# Nebenplatine.net
KiCad netlist of a schematic drawn in EAGLE
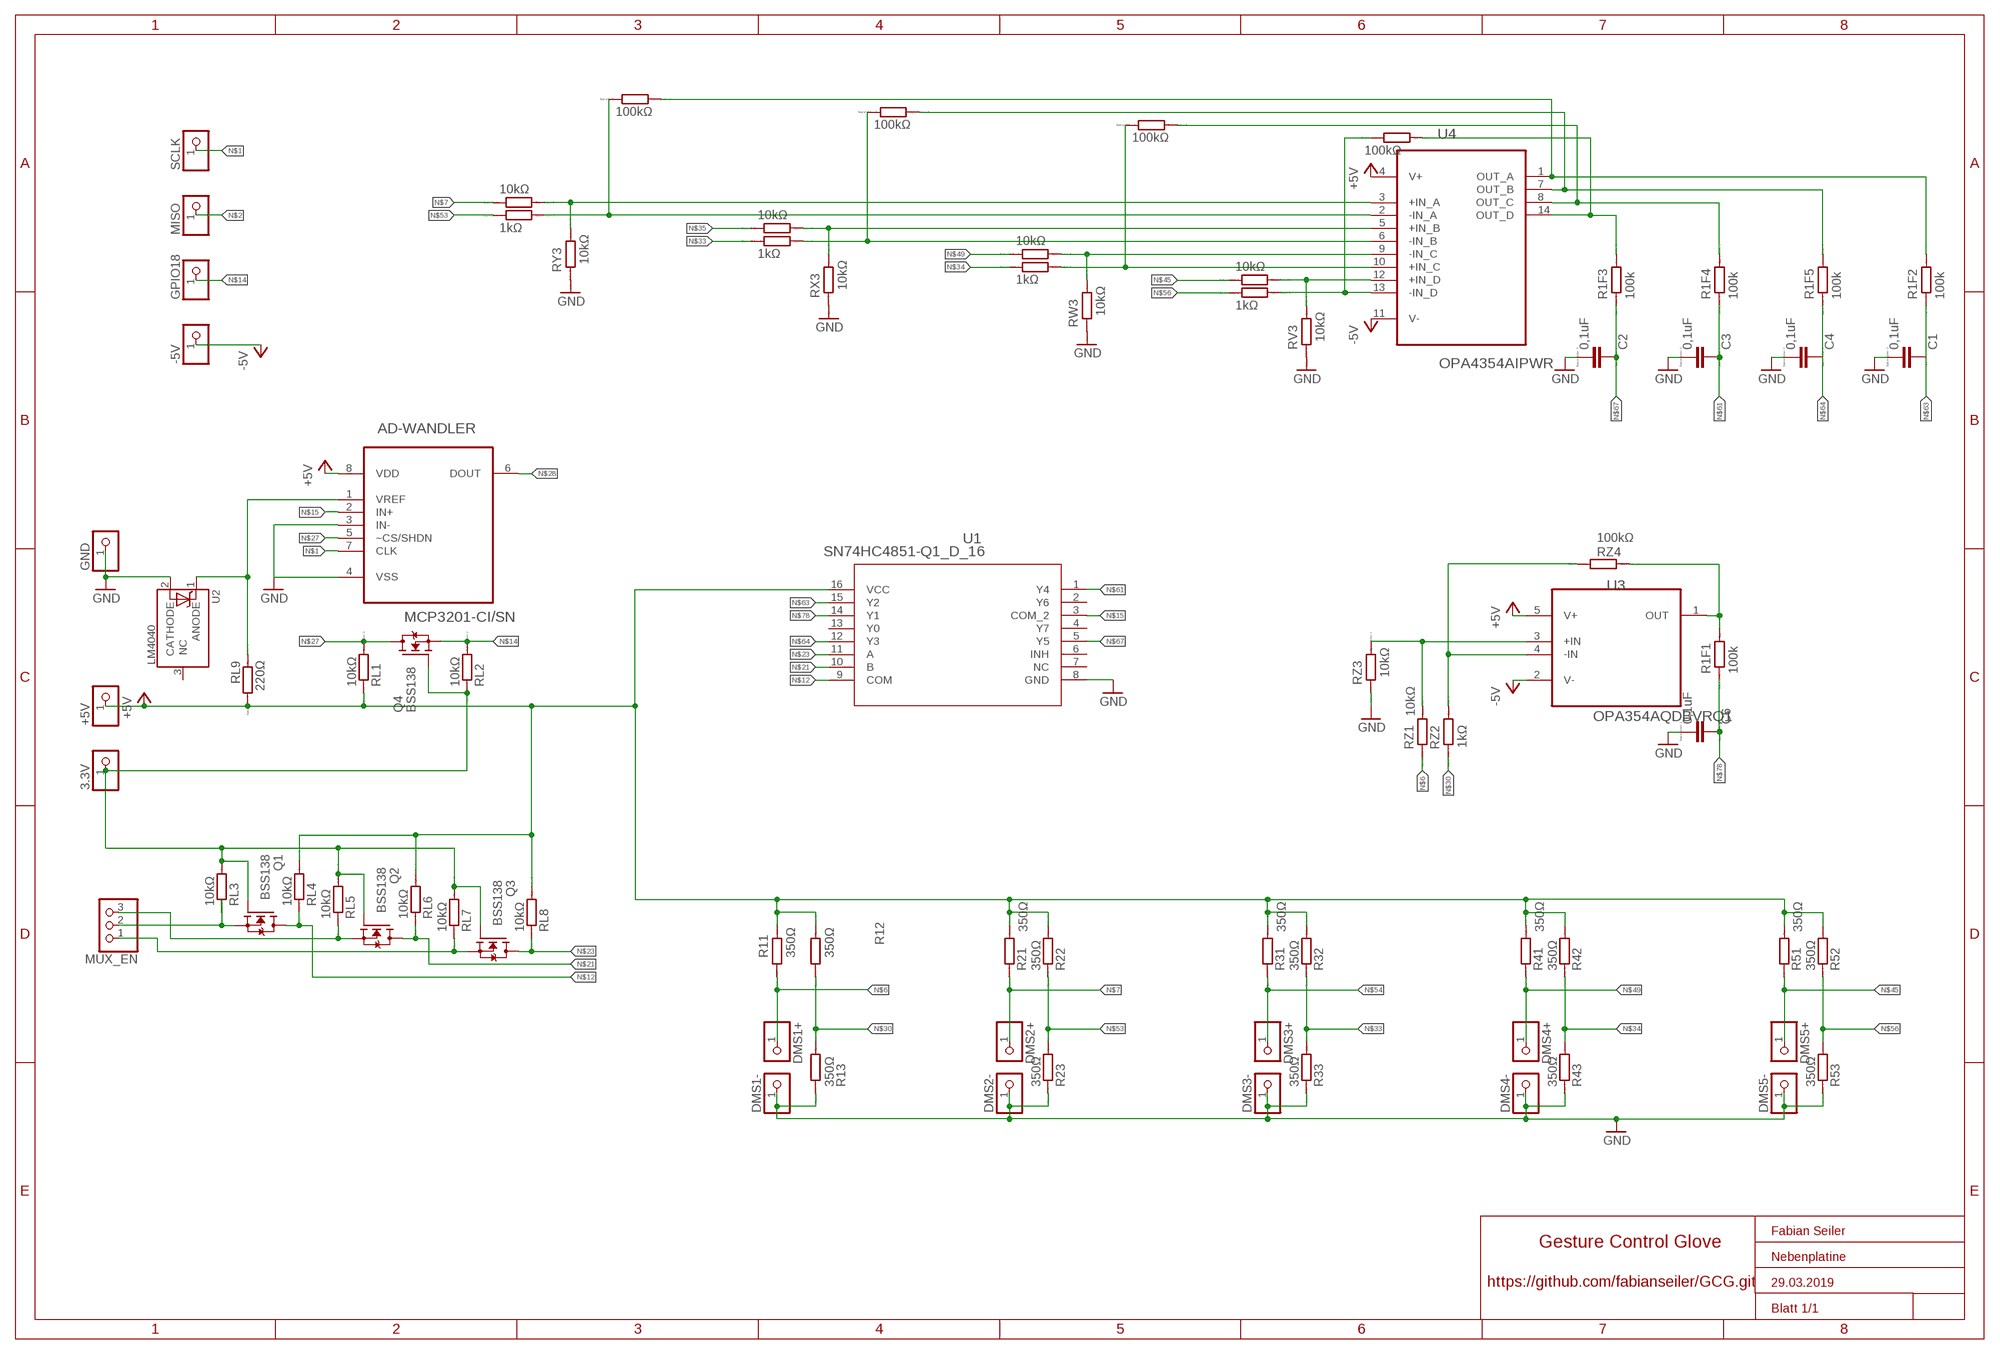
[diagram p0: schematic, sheet 1]

(export (version "E")
  (design (tool "Eeschema 10.0.6"))
  (components
    (comp (ref "+5V")
      (value "PINHD-1X1CB")
      (footprint "eagle-import:1X01-CLEANBIG")
      (libsource (lib "eagle-import") (part "PINHD-1X1CB"))
    )
    (comp (ref "-5V")
      (value "PINHD-1X1CB")
      (footprint "eagle-import:1X01-CLEANBIG")
      (libsource (lib "eagle-import") (part "PINHD-1X1CB"))
    )
    (comp (ref "3.3V")
      (value "PINHD-1X1CB")
      (footprint "eagle-import:1X01-CLEANBIG")
      (libsource (lib "eagle-import") (part "PINHD-1X1CB"))
    )
    (comp (ref "AD-WANDLER")
      (value "MCP3201-CI/SN")
      (footprint "eagle-import:SOIC127P600X175-8N")
      (fields (field (name "MF") "Microchip"))
      (libsource (lib "eagle-import") (part "MCP3201-CI/SN"))
    )
    (comp (ref "C1")
      (value "0,1uF")
      (footprint "eagle-import:C0402")
      (libsource (lib "eagle-import") (part "C-EUC0402"))
    )
    (comp (ref "C2")
      (value "0,1uF")
      (footprint "eagle-import:C0402")
      (libsource (lib "eagle-import") (part "C-EUC0402"))
    )
    (comp (ref "C3")
      (value "0,1uF")
      (footprint "eagle-import:C0402")
      (libsource (lib "eagle-import") (part "C-EUC0402"))
    )
    (comp (ref "C4")
      (value "0,1uF")
      (footprint "eagle-import:C0402")
      (libsource (lib "eagle-import") (part "C-EUC0402"))
    )
    (comp (ref "C6")
      (value "0,1uF")
      (footprint "eagle-import:C0402")
      (libsource (lib "eagle-import") (part "C-EUC0402"))
    )
    (comp (ref "DMS1+")
      (value "PINHD-1X1CB")
      (footprint "eagle-import:1X01-CLEANBIG")
      (libsource (lib "eagle-import") (part "PINHD-1X1CB"))
    )
    (comp (ref "DMS1-")
      (value "PINHD-1X1CB")
      (footprint "eagle-import:1X01-CLEANBIG")
      (libsource (lib "eagle-import") (part "PINHD-1X1CB"))
    )
    (comp (ref "DMS2+")
      (value "PINHD-1X1CB")
      (footprint "eagle-import:1X01-CLEANBIG")
      (libsource (lib "eagle-import") (part "PINHD-1X1CB"))
    )
    (comp (ref "DMS2-")
      (value "PINHD-1X1CB")
      (footprint "eagle-import:1X01-CLEANBIG")
      (libsource (lib "eagle-import") (part "PINHD-1X1CB"))
    )
    (comp (ref "DMS3+")
      (value "PINHD-1X1CB")
      (footprint "eagle-import:1X01-CLEANBIG")
      (libsource (lib "eagle-import") (part "PINHD-1X1CB"))
    )
    (comp (ref "DMS3-")
      (value "PINHD-1X1CB")
      (footprint "eagle-import:1X01-CLEANBIG")
      (libsource (lib "eagle-import") (part "PINHD-1X1CB"))
    )
    (comp (ref "DMS4+")
      (value "PINHD-1X1CB")
      (footprint "eagle-import:1X01-CLEANBIG")
      (libsource (lib "eagle-import") (part "PINHD-1X1CB"))
    )
    (comp (ref "DMS4-")
      (value "PINHD-1X1CB")
      (footprint "eagle-import:1X01-CLEANBIG")
      (libsource (lib "eagle-import") (part "PINHD-1X1CB"))
    )
    (comp (ref "DMS5+")
      (value "PINHD-1X1CB")
      (footprint "eagle-import:1X01-CLEANBIG")
      (libsource (lib "eagle-import") (part "PINHD-1X1CB"))
    )
    (comp (ref "DMS5-")
      (value "PINHD-1X1CB")
      (footprint "eagle-import:1X01-CLEANBIG")
      (libsource (lib "eagle-import") (part "PINHD-1X1CB"))
    )
    (comp (ref "GND")
      (value "PINHD-1X1CB")
      (footprint "eagle-import:1X01-CLEANBIG")
      (libsource (lib "eagle-import") (part "PINHD-1X1CB"))
    )
    (comp (ref "GPIO18")
      (value "PINHD-1X1CB")
      (footprint "eagle-import:1X01-CLEANBIG")
      (libsource (lib "eagle-import") (part "PINHD-1X1CB"))
    )
    (comp (ref "MISO")
      (value "PINHD-1X1CB")
      (footprint "eagle-import:1X01-CLEANBIG")
      (libsource (lib "eagle-import") (part "PINHD-1X1CB"))
    )
    (comp (ref "MUX_EN")
      (value "PINHD-1X3CB")
      (footprint "eagle-import:1X03-CLEANBIG")
      (libsource (lib "eagle-import") (part "PINHD-1X3CB"))
    )
    (comp (ref "Q1")
      (value "BSS138")
      (footprint "eagle-import:SOT23")
      (fields (field (name "MF") "Fairchild"))
      (libsource (lib "eagle-import") (part "BSS138"))
    )
    (comp (ref "Q2")
      (value "BSS138")
      (footprint "eagle-import:SOT23")
      (fields (field (name "MF") "Fairchild"))
      (libsource (lib "eagle-import") (part "BSS138"))
    )
    (comp (ref "Q3")
      (value "BSS138")
      (footprint "eagle-import:SOT23")
      (fields (field (name "MF") "Fairchild"))
      (libsource (lib "eagle-import") (part "BSS138"))
    )
    (comp (ref "Q4")
      (value "BSS138")
      (footprint "eagle-import:SOT23")
      (fields (field (name "MF") "Fairchild"))
      (libsource (lib "eagle-import") (part "BSS138"))
    )
    (comp (ref "R1F1")
      (value "100k")
      (footprint "eagle-import:R0402")
      (libsource (lib "eagle-import") (part "R-EU_R0402"))
    )
    (comp (ref "R1F2")
      (value "100k")
      (footprint "eagle-import:R0402")
      (libsource (lib "eagle-import") (part "R-EU_R0402"))
    )
    (comp (ref "R1F3")
      (value "100k")
      (footprint "eagle-import:R0402")
      (libsource (lib "eagle-import") (part "R-EU_R0402"))
    )
    (comp (ref "R1F4")
      (value "100k")
      (footprint "eagle-import:R0402")
      (libsource (lib "eagle-import") (part "R-EU_R0402"))
    )
    (comp (ref "R1F5")
      (value "100k")
      (footprint "eagle-import:R0402")
      (libsource (lib "eagle-import") (part "R-EU_R0402"))
    )
    (comp (ref "R11")
      (value "350Ω")
      (footprint "eagle-import:R0402")
      (libsource (lib "eagle-import") (part "R-EU_R0402"))
    )
    (comp (ref "R12")
      (value "350Ω")
      (footprint "eagle-import:R0402")
      (libsource (lib "eagle-import") (part "R-EU_R0402"))
    )
    (comp (ref "R13")
      (value "350Ω")
      (footprint "eagle-import:R0402")
      (libsource (lib "eagle-import") (part "R-EU_R0402"))
    )
    (comp (ref "R21")
      (value "350Ω")
      (footprint "eagle-import:R0402")
      (libsource (lib "eagle-import") (part "R-EU_R0402"))
    )
    (comp (ref "R22")
      (value "350Ω")
      (footprint "eagle-import:R0402")
      (libsource (lib "eagle-import") (part "R-EU_R0402"))
    )
    (comp (ref "R23")
      (value "350Ω")
      (footprint "eagle-import:R0402")
      (libsource (lib "eagle-import") (part "R-EU_R0402"))
    )
    (comp (ref "R31")
      (value "350Ω")
      (footprint "eagle-import:R0402")
      (libsource (lib "eagle-import") (part "R-EU_R0402"))
    )
    (comp (ref "R32")
      (value "350Ω")
      (footprint "eagle-import:R0402")
      (libsource (lib "eagle-import") (part "R-EU_R0402"))
    )
    (comp (ref "R33")
      (value "350Ω")
      (footprint "eagle-import:R0402")
      (libsource (lib "eagle-import") (part "R-EU_R0402"))
    )
    (comp (ref "R41")
      (value "350Ω")
      (footprint "eagle-import:R0402")
      (libsource (lib "eagle-import") (part "R-EU_R0402"))
    )
    (comp (ref "R42")
      (value "350Ω")
      (footprint "eagle-import:R0402")
      (libsource (lib "eagle-import") (part "R-EU_R0402"))
    )
    (comp (ref "R43")
      (value "350Ω")
      (footprint "eagle-import:R0402")
      (libsource (lib "eagle-import") (part "R-EU_R0402"))
    )
    (comp (ref "R51")
      (value "350Ω")
      (footprint "eagle-import:R0402")
      (libsource (lib "eagle-import") (part "R-EU_R0402"))
    )
    (comp (ref "R52")
      (value "350Ω")
      (footprint "eagle-import:R0402")
      (libsource (lib "eagle-import") (part "R-EU_R0402"))
    )
    (comp (ref "R53")
      (value "350Ω")
      (footprint "eagle-import:R0402")
      (libsource (lib "eagle-import") (part "R-EU_R0402"))
    )
    (comp (ref "RL1")
      (value "10kΩ")
      (footprint "eagle-import:R0402")
      (libsource (lib "eagle-import") (part "R-EU_R0402"))
    )
    (comp (ref "RL2")
      (value "10kΩ")
      (footprint "eagle-import:R0402")
      (libsource (lib "eagle-import") (part "R-EU_R0402"))
    )
    (comp (ref "RL3")
      (value "10kΩ")
      (footprint "eagle-import:R0402")
      (libsource (lib "eagle-import") (part "R-EU_R0402"))
    )
    (comp (ref "RL4")
      (value "10kΩ")
      (footprint "eagle-import:R0402")
      (libsource (lib "eagle-import") (part "R-EU_R0402"))
    )
    (comp (ref "RL5")
      (value "10kΩ")
      (footprint "eagle-import:R0402")
      (libsource (lib "eagle-import") (part "R-EU_R0402"))
    )
    (comp (ref "RL6")
      (value "10kΩ")
      (footprint "eagle-import:R0402")
      (libsource (lib "eagle-import") (part "R-EU_R0402"))
    )
    (comp (ref "RL7")
      (value "10kΩ")
      (footprint "eagle-import:R0402")
      (libsource (lib "eagle-import") (part "R-EU_R0402"))
    )
    (comp (ref "RL8")
      (value "10kΩ")
      (footprint "eagle-import:R0402")
      (libsource (lib "eagle-import") (part "R-EU_R0402"))
    )
    (comp (ref "RL9")
      (value "220Ω")
      (footprint "eagle-import:R0402")
      (libsource (lib "eagle-import") (part "R-EU_R0402"))
    )
    (comp (ref "RV1")
      (value "1kΩ")
      (footprint "eagle-import:R0402")
      (libsource (lib "eagle-import") (part "R-EU_R0402"))
    )
    (comp (ref "RV2")
      (value "10kΩ")
      (footprint "eagle-import:R0402")
      (libsource (lib "eagle-import") (part "R-EU_R0402"))
    )
    (comp (ref "RV3")
      (value "10kΩ")
      (footprint "eagle-import:R0402")
      (libsource (lib "eagle-import") (part "R-EU_R0402"))
    )
    (comp (ref "RV4")
      (value "100kΩ")
      (footprint "eagle-import:R0402")
      (libsource (lib "eagle-import") (part "R-EU_R0402"))
    )
    (comp (ref "RW1")
      (value "1kΩ")
      (footprint "eagle-import:R0402")
      (libsource (lib "eagle-import") (part "R-EU_R0402"))
    )
    (comp (ref "RW2")
      (value "10kΩ")
      (footprint "eagle-import:R0402")
      (libsource (lib "eagle-import") (part "R-EU_R0402"))
    )
    (comp (ref "RW3")
      (value "10kΩ")
      (footprint "eagle-import:R0402")
      (libsource (lib "eagle-import") (part "R-EU_R0402"))
    )
    (comp (ref "RW4")
      (value "100kΩ")
      (footprint "eagle-import:R0402")
      (libsource (lib "eagle-import") (part "R-EU_R0402"))
    )
    (comp (ref "RX1")
      (value "1kΩ")
      (footprint "eagle-import:R0402")
      (libsource (lib "eagle-import") (part "R-EU_R0402"))
    )
    (comp (ref "RX2")
      (value "10kΩ")
      (footprint "eagle-import:R0402")
      (libsource (lib "eagle-import") (part "R-EU_R0402"))
    )
    (comp (ref "RX3")
      (value "10kΩ")
      (footprint "eagle-import:R0402")
      (libsource (lib "eagle-import") (part "R-EU_R0402"))
    )
    (comp (ref "RX4")
      (value "100kΩ")
      (footprint "eagle-import:R0402")
      (libsource (lib "eagle-import") (part "R-EU_R0402"))
    )
    (comp (ref "RY1")
      (value "10kΩ")
      (footprint "eagle-import:R0402")
      (libsource (lib "eagle-import") (part "R-EU_R0402"))
    )
    (comp (ref "RY2")
      (value "1kΩ")
      (footprint "eagle-import:R0402")
      (libsource (lib "eagle-import") (part "R-EU_R0402"))
    )
    (comp (ref "RY3")
      (value "10kΩ")
      (footprint "eagle-import:R0402")
      (libsource (lib "eagle-import") (part "R-EU_R0402"))
    )
    (comp (ref "RY4")
      (value "100kΩ")
      (footprint "eagle-import:R0402")
      (libsource (lib "eagle-import") (part "R-EU_R0402"))
    )
    (comp (ref "RZ1")
      (value "10kΩ")
      (footprint "eagle-import:R0402")
      (libsource (lib "eagle-import") (part "R-EU_R0402"))
    )
    (comp (ref "RZ2")
      (value "1kΩ")
      (footprint "eagle-import:R0402")
      (libsource (lib "eagle-import") (part "R-EU_R0402"))
    )
    (comp (ref "RZ3")
      (value "10kΩ")
      (footprint "eagle-import:R0402")
      (libsource (lib "eagle-import") (part "R-EU_R0402"))
    )
    (comp (ref "RZ4")
      (value "100kΩ")
      (footprint "eagle-import:R0402")
      (libsource (lib "eagle-import") (part "R-EU_R0402"))
    )
    (comp (ref "SCLK")
      (value "PINHD-1X1CB")
      (footprint "eagle-import:1X01-CLEANBIG")
      (libsource (lib "eagle-import") (part "PINHD-1X1CB"))
    )
    (comp (ref "U1")
      (value "SN74HC4851-Q1_D_16")
      (footprint "eagle-import:D16")
      (fields (field (name "MANUFACTURER_PART_NUMBER") "SN74HC4851Q1_D_16"))
      (libsource (lib "eagle-import") (part "SN74HC4851-Q1_D_16"))
    )
    (comp (ref "U2")
      (value "LM4040")
      (footprint "eagle-import:SOT23-3")
      (fields (field (name "MF") "Amphenol"))
      (libsource (lib "eagle-import") (part "LM4040"))
    )
    (comp (ref "U3")
      (value "OPA354AQDBVRQ1")
      (footprint "eagle-import:SOT95P280X145-5N")
      (fields (field (name "MF") "Texas Instruments"))
      (libsource (lib "eagle-import") (part "OPA354AQDBVRQ1"))
    )
    (comp (ref "U4")
      (value "OPA4354AIPWR")
      (footprint "eagle-import:SOP65P640X120-14N")
      (fields (field (name "MF") "Texas Instruments"))
      (libsource (lib "eagle-import") (part "OPA4354AIPWR"))
    )
  )
  (nets
    (net (code "1") (name "+5V") (class "Default")
      (node (ref "+5V") (pin "1") (pinfunction "1_1") (pintype "passive"))
      (node (ref "AD-WANDLER") (pin "8") (pinfunction "VDD_8") (pintype "power_in"))
      (node (ref "R11") (pin "2") (pinfunction "2_2") (pintype "passive"))
      (node (ref "R12") (pin "2") (pinfunction "2_2") (pintype "passive"))
      (node (ref "R21") (pin "2") (pinfunction "2_2") (pintype "passive"))
      (node (ref "R22") (pin "2") (pinfunction "2_2") (pintype "passive"))
      (node (ref "R31") (pin "2") (pinfunction "2_2") (pintype "passive"))
      (node (ref "R32") (pin "2") (pinfunction "2_2") (pintype "passive"))
      (node (ref "R41") (pin "2") (pinfunction "2_2") (pintype "passive"))
      (node (ref "R42") (pin "2") (pinfunction "2_2") (pintype "passive"))
      (node (ref "R51") (pin "2") (pinfunction "2_2") (pintype "passive"))
      (node (ref "R52") (pin "2") (pinfunction "2_2") (pintype "passive"))
      (node (ref "RL1") (pin "1") (pinfunction "1_1") (pintype "passive"))
      (node (ref "RL4") (pin "2") (pinfunction "2_2") (pintype "passive"))
      (node (ref "RL6") (pin "2") (pinfunction "2_2") (pintype "passive"))
      (node (ref "RL8") (pin "2") (pinfunction "2_2") (pintype "passive"))
      (node (ref "RL9") (pin "2") (pinfunction "2_2") (pintype "passive"))
      (node (ref "U1") (pin "16") (pinfunction "VCC_16") (pintype "power_in"))
      (node (ref "U3") (pin "5") (pinfunction "V+_5") (pintype "power_in"))
      (node (ref "U4") (pin "4") (pinfunction "V+_4") (pintype "power_in"))
    )
    (net (code "2") (name "-5V") (class "Default")
      (node (ref "-5V") (pin "1") (pinfunction "1_1") (pintype "passive"))
      (node (ref "U3") (pin "2") (pinfunction "V-_2") (pintype "power_in"))
      (node (ref "U4") (pin "11") (pinfunction "V-_11") (pintype "power_in"))
    )
    (net (code "3") (name "GND") (class "Default")
      (node (ref "AD-WANDLER") (pin "3") (pinfunction "IN-_3") (pintype "input"))
      (node (ref "AD-WANDLER") (pin "4") (pinfunction "VSS_4") (pintype "power_in"))
      (node (ref "C1") (pin "2") (pinfunction "2_2") (pintype "passive"))
      (node (ref "C2") (pin "2") (pinfunction "2_2") (pintype "passive"))
      (node (ref "C3") (pin "2") (pinfunction "2_2") (pintype "passive"))
      (node (ref "C4") (pin "2") (pinfunction "2_2") (pintype "passive"))
      (node (ref "C6") (pin "2") (pinfunction "2_2") (pintype "passive"))
      (node (ref "DMS1-") (pin "1") (pinfunction "1_1") (pintype "passive"))
      (node (ref "DMS2-") (pin "1") (pinfunction "1_1") (pintype "passive"))
      (node (ref "DMS3-") (pin "1") (pinfunction "1_1") (pintype "passive"))
      (node (ref "DMS4-") (pin "1") (pinfunction "1_1") (pintype "passive"))
      (node (ref "DMS5-") (pin "1") (pinfunction "1_1") (pintype "passive"))
      (node (ref "GND") (pin "1") (pinfunction "1_1") (pintype "passive"))
      (node (ref "R13") (pin "1") (pinfunction "1_1") (pintype "passive"))
      (node (ref "R23") (pin "1") (pinfunction "1_1") (pintype "passive"))
      (node (ref "R33") (pin "1") (pinfunction "1_1") (pintype "passive"))
      (node (ref "R43") (pin "1") (pinfunction "1_1") (pintype "passive"))
      (node (ref "R53") (pin "1") (pinfunction "1_1") (pintype "passive"))
      (node (ref "RV3") (pin "2") (pinfunction "2_2") (pintype "passive"))
      (node (ref "RW3") (pin "2") (pinfunction "2_2") (pintype "passive"))
      (node (ref "RX3") (pin "2") (pinfunction "2_2") (pintype "passive"))
      (node (ref "RY3") (pin "2") (pinfunction "2_2") (pintype "passive"))
      (node (ref "RZ3") (pin "2") (pinfunction "2_2") (pintype "passive"))
      (node (ref "U1") (pin "8") (pinfunction "GND_8") (pintype "power_in"))
      (node (ref "U2") (pin "2") (pinfunction "CATHODE_2") (pintype "bidirectional"))
    )
    (net (code "4") (name "N$1") (class "Default")
      (node (ref "AD-WANDLER") (pin "7") (pinfunction "CLK_7") (pintype "input"))
      (node (ref "SCLK") (pin "1") (pinfunction "1_1") (pintype "passive"))
    )
    (net (code "5") (name "N$2") (class "Default")
      (node (ref "MISO") (pin "1") (pinfunction "1_1") (pintype "passive"))
    )
    (net (code "6") (name "N$6") (class "Default")
      (node (ref "DMS1+") (pin "1") (pinfunction "1_1") (pintype "passive"))
      (node (ref "R11") (pin "1") (pinfunction "1_1") (pintype "passive"))
      (node (ref "RZ1") (pin "2") (pinfunction "2_2") (pintype "passive"))
    )
    (net (code "7") (name "N$7") (class "Default")
      (node (ref "DMS2+") (pin "1") (pinfunction "1_1") (pintype "passive"))
      (node (ref "R21") (pin "1") (pinfunction "1_1") (pintype "passive"))
      (node (ref "RY1") (pin "1") (pinfunction "1_1") (pintype "passive"))
    )
    (net (code "8") (name "N$12") (class "Default")
      (node (ref "Q1") (pin "3") (pinfunction "D_3") (pintype "passive"))
      (node (ref "RL4") (pin "1") (pinfunction "1_1") (pintype "passive"))
      (node (ref "U1") (pin "9") (pinfunction "COM_9") (pintype "input"))
    )
    (net (code "9") (name "N$14") (class "Default")
      (node (ref "GPIO18") (pin "1") (pinfunction "1_1") (pintype "passive"))
      (node (ref "Q4") (pin "2") (pinfunction "S_2") (pintype "passive"))
      (node (ref "RL2") (pin "2") (pinfunction "2_2") (pintype "passive"))
    )
    (net (code "10") (name "N$15") (class "Default")
      (node (ref "AD-WANDLER") (pin "2") (pinfunction "IN+_2") (pintype "input"))
      (node (ref "U1") (pin "3") (pinfunction "COM_2_3") (pintype "input"))
    )
    (net (code "11") (name "N$21") (class "Default")
      (node (ref "Q2") (pin "3") (pinfunction "D_3") (pintype "passive"))
      (node (ref "RL6") (pin "1") (pinfunction "1_1") (pintype "passive"))
      (node (ref "U1") (pin "10") (pinfunction "B_10") (pintype "input"))
    )
    (net (code "12") (name "N$23") (class "Default")
      (node (ref "Q3") (pin "3") (pinfunction "D_3") (pintype "passive"))
      (node (ref "RL8") (pin "1") (pinfunction "1_1") (pintype "passive"))
      (node (ref "U1") (pin "11") (pinfunction "A_11") (pintype "input"))
    )
    (net (code "13") (name "N$27") (class "Default")
      (node (ref "AD-WANDLER") (pin "5") (pinfunction "~{CS/SHDN}_5") (pintype "input"))
      (node (ref "Q4") (pin "3") (pinfunction "D_3") (pintype "passive"))
      (node (ref "RL1") (pin "2") (pinfunction "2_2") (pintype "passive"))
    )
    (net (code "14") (name "N$28") (class "Default")
      (node (ref "AD-WANDLER") (pin "6") (pinfunction "DOUT_6") (pintype "output"))
    )
    (net (code "15") (name "N$30") (class "Default")
      (node (ref "R12") (pin "1") (pinfunction "1_1") (pintype "passive"))
      (node (ref "R13") (pin "2") (pinfunction "2_2") (pintype "passive"))
      (node (ref "RZ2") (pin "2") (pinfunction "2_2") (pintype "passive"))
    )
    (net (code "16") (name "N$33") (class "Default")
      (node (ref "R32") (pin "1") (pinfunction "1_1") (pintype "passive"))
      (node (ref "R33") (pin "2") (pinfunction "2_2") (pintype "passive"))
      (node (ref "RX1") (pin "1") (pinfunction "1_1") (pintype "passive"))
    )
    (net (code "17") (name "N$34") (class "Default")
      (node (ref "R42") (pin "1") (pinfunction "1_1") (pintype "passive"))
      (node (ref "R43") (pin "2") (pinfunction "2_2") (pintype "passive"))
      (node (ref "RW1") (pin "1") (pinfunction "1_1") (pintype "passive"))
    )
    (net (code "18") (name "N$35") (class "Default")
      (node (ref "RX2") (pin "1") (pinfunction "1_1") (pintype "passive"))
    )
    (net (code "19") (name "N$45") (class "Default")
      (node (ref "DMS5+") (pin "1") (pinfunction "1_1") (pintype "passive"))
      (node (ref "R51") (pin "1") (pinfunction "1_1") (pintype "passive"))
      (node (ref "RV2") (pin "1") (pinfunction "1_1") (pintype "passive"))
    )
    (net (code "20") (name "N$49") (class "Default")
      (node (ref "DMS4+") (pin "1") (pinfunction "1_1") (pintype "passive"))
      (node (ref "R41") (pin "1") (pinfunction "1_1") (pintype "passive"))
      (node (ref "RW2") (pin "1") (pinfunction "1_1") (pintype "passive"))
    )
    (net (code "21") (name "N$53") (class "Default")
      (node (ref "R22") (pin "1") (pinfunction "1_1") (pintype "passive"))
      (node (ref "R23") (pin "2") (pinfunction "2_2") (pintype "passive"))
      (node (ref "RY2") (pin "1") (pinfunction "1_1") (pintype "passive"))
    )
    (net (code "22") (name "N$54") (class "Default")
      (node (ref "DMS3+") (pin "1") (pinfunction "1_1") (pintype "passive"))
      (node (ref "R31") (pin "1") (pinfunction "1_1") (pintype "passive"))
      (node (ref "RY2") (pin "2") (pinfunction "2_2") (pintype "passive"))
      (node (ref "RY4") (pin "1") (pinfunction "1_1") (pintype "passive"))
      (node (ref "U4") (pin "2") (pinfunction "-IN_A_2") (pintype "input"))
    )
    (net (code "23") (name "N$56") (class "Default")
      (node (ref "R52") (pin "1") (pinfunction "1_1") (pintype "passive"))
      (node (ref "R53") (pin "2") (pinfunction "2_2") (pintype "passive"))
      (node (ref "RV1") (pin "1") (pinfunction "1_1") (pintype "passive"))
    )
    (net (code "24") (name "N$61") (class "Default")
      (node (ref "C3") (pin "1") (pinfunction "1_1") (pintype "passive"))
      (node (ref "R1F4") (pin "1") (pinfunction "1_1") (pintype "passive"))
      (node (ref "U1") (pin "1") (pinfunction "Y4_1") (pintype "output"))
    )
    (net (code "25") (name "N$63") (class "Default")
      (node (ref "C1") (pin "1") (pinfunction "1_1") (pintype "passive"))
      (node (ref "R1F2") (pin "1") (pinfunction "1_1") (pintype "passive"))
      (node (ref "U1") (pin "15") (pinfunction "Y2_15") (pintype "output"))
    )
    (net (code "26") (name "N$64") (class "Default")
      (node (ref "C4") (pin "1") (pinfunction "1_1") (pintype "passive"))
      (node (ref "R1F5") (pin "1") (pinfunction "1_1") (pintype "passive"))
      (node (ref "U1") (pin "12") (pinfunction "Y3_12") (pintype "output"))
    )
    (net (code "27") (name "N$67") (class "Default")
      (node (ref "C2") (pin "1") (pinfunction "1_1") (pintype "passive"))
      (node (ref "R1F3") (pin "1") (pinfunction "1_1") (pintype "passive"))
      (node (ref "U1") (pin "5") (pinfunction "Y5_5") (pintype "output"))
    )
    (net (code "28") (name "N$78") (class "Default")
      (node (ref "C6") (pin "1") (pinfunction "1_1") (pintype "passive"))
      (node (ref "R1F1") (pin "1") (pinfunction "1_1") (pintype "passive"))
      (node (ref "U1") (pin "14") (pinfunction "Y1_14") (pintype "output"))
    )
    (net (code "29") (name "Net-(AD-WANDLER-VREF)") (class "Default")
      (node (ref "AD-WANDLER") (pin "1") (pinfunction "VREF_1") (pintype "input"))
      (node (ref "RL9") (pin "1") (pinfunction "1_1") (pintype "passive"))
      (node (ref "U2") (pin "1") (pinfunction "ANODE_1") (pintype "bidirectional"))
    )
    (net (code "30") (name "Net-(Q1-G)") (class "Default")
      (node (ref "3.3V") (pin "1") (pinfunction "1_1") (pintype "passive"))
      (node (ref "Q1") (pin "1") (pinfunction "G_1") (pintype "passive"))
      (node (ref "Q2") (pin "1") (pinfunction "G_1") (pintype "passive"))
      (node (ref "Q3") (pin "1") (pinfunction "G_1") (pintype "passive"))
      (node (ref "Q4") (pin "1") (pinfunction "G_1") (pintype "passive"))
      (node (ref "RL2") (pin "1") (pinfunction "1_1") (pintype "passive"))
      (node (ref "RL3") (pin "2") (pinfunction "2_2") (pintype "passive"))
      (node (ref "RL5") (pin "2") (pinfunction "2_2") (pintype "passive"))
      (node (ref "RL7") (pin "2") (pinfunction "2_2") (pintype "passive"))
    )
    (net (code "31") (name "Net-(Q1-S)") (class "Default")
      (node (ref "MUX_EN") (pin "2") (pinfunction "2_2") (pintype "passive"))
      (node (ref "Q1") (pin "2") (pinfunction "S_2") (pintype "passive"))
      (node (ref "RL3") (pin "1") (pinfunction "1_1") (pintype "passive"))
    )
    (net (code "32") (name "Net-(Q2-S)") (class "Default")
      (node (ref "MUX_EN") (pin "3") (pinfunction "3_3") (pintype "passive"))
      (node (ref "Q2") (pin "2") (pinfunction "S_2") (pintype "passive"))
      (node (ref "RL5") (pin "1") (pinfunction "1_1") (pintype "passive"))
    )
    (net (code "33") (name "Net-(Q3-S)") (class "Default")
      (node (ref "MUX_EN") (pin "1") (pinfunction "1_1") (pintype "passive"))
      (node (ref "Q3") (pin "2") (pinfunction "S_2") (pintype "passive"))
      (node (ref "RL7") (pin "1") (pinfunction "1_1") (pintype "passive"))
    )
    (net (code "34") (name "Net-(U3-+IN)") (class "Default")
      (node (ref "RZ1") (pin "1") (pinfunction "1_1") (pintype "passive"))
      (node (ref "RZ3") (pin "1") (pinfunction "1_1") (pintype "passive"))
      (node (ref "U3") (pin "3") (pinfunction "+IN_3") (pintype "input"))
    )
    (net (code "35") (name "Net-(U3--IN)") (class "Default")
      (node (ref "RZ2") (pin "1") (pinfunction "1_1") (pintype "passive"))
      (node (ref "RZ4") (pin "1") (pinfunction "1_1") (pintype "passive"))
      (node (ref "U3") (pin "4") (pinfunction "-IN_4") (pintype "input"))
    )
    (net (code "36") (name "Net-(U3-OUT)") (class "Default")
      (node (ref "R1F1") (pin "2") (pinfunction "2_2") (pintype "passive"))
      (node (ref "RZ4") (pin "2") (pinfunction "2_2") (pintype "passive"))
      (node (ref "U3") (pin "1") (pinfunction "OUT_1") (pintype "output"))
    )
    (net (code "37") (name "Net-(U4-+IN_A)") (class "Default")
      (node (ref "RY1") (pin "2") (pinfunction "2_2") (pintype "passive"))
      (node (ref "RY3") (pin "1") (pinfunction "1_1") (pintype "passive"))
      (node (ref "U4") (pin "3") (pinfunction "+IN_A_3") (pintype "input"))
    )
    (net (code "38") (name "Net-(U4-+IN_B)") (class "Default")
      (node (ref "RX2") (pin "2") (pinfunction "2_2") (pintype "passive"))
      (node (ref "RX3") (pin "1") (pinfunction "1_1") (pintype "passive"))
      (node (ref "U4") (pin "5") (pinfunction "+IN_B_5") (pintype "input"))
    )
    (net (code "39") (name "Net-(U4-+IN_C)") (class "Default")
      (node (ref "RW1") (pin "2") (pinfunction "2_2") (pintype "passive"))
      (node (ref "RW4") (pin "1") (pinfunction "1_1") (pintype "passive"))
      (node (ref "U4") (pin "10") (pinfunction "+IN_C_10") (pintype "input"))
    )
    (net (code "40") (name "Net-(U4-+IN_D)") (class "Default")
      (node (ref "RV2") (pin "2") (pinfunction "2_2") (pintype "passive"))
      (node (ref "RV3") (pin "1") (pinfunction "1_1") (pintype "passive"))
      (node (ref "U4") (pin "12") (pinfunction "+IN_D_12") (pintype "input"))
    )
    (net (code "41") (name "Net-(U4--IN_B)") (class "Default")
      (node (ref "RX1") (pin "2") (pinfunction "2_2") (pintype "passive"))
      (node (ref "RX4") (pin "1") (pinfunction "1_1") (pintype "passive"))
      (node (ref "U4") (pin "6") (pinfunction "-IN_B_6") (pintype "input"))
    )
    (net (code "42") (name "Net-(U4--IN_C)") (class "Default")
      (node (ref "RW2") (pin "2") (pinfunction "2_2") (pintype "passive"))
      (node (ref "RW3") (pin "1") (pinfunction "1_1") (pintype "passive"))
      (node (ref "U4") (pin "9") (pinfunction "-IN_C_9") (pintype "input"))
    )
    (net (code "43") (name "Net-(U4--IN_D)") (class "Default")
      (node (ref "RV1") (pin "2") (pinfunction "2_2") (pintype "passive"))
      (node (ref "RV4") (pin "1") (pinfunction "1_1") (pintype "passive"))
      (node (ref "U4") (pin "13") (pinfunction "-IN_D_13") (pintype "input"))
    )
    (net (code "44") (name "Net-(U4-OUT_A)") (class "Default")
      (node (ref "R1F2") (pin "2") (pinfunction "2_2") (pintype "passive"))
      (node (ref "RY4") (pin "2") (pinfunction "2_2") (pintype "passive"))
      (node (ref "U4") (pin "1") (pinfunction "OUT_A_1") (pintype "output"))
    )
    (net (code "45") (name "Net-(U4-OUT_B)") (class "Default")
      (node (ref "R1F5") (pin "2") (pinfunction "2_2") (pintype "passive"))
      (node (ref "RX4") (pin "2") (pinfunction "2_2") (pintype "passive"))
      (node (ref "U4") (pin "7") (pinfunction "OUT_B_7") (pintype "output"))
    )
    (net (code "46") (name "Net-(U4-OUT_C)") (class "Default")
      (node (ref "R1F4") (pin "2") (pinfunction "2_2") (pintype "passive"))
      (node (ref "RW4") (pin "2") (pinfunction "2_2") (pintype "passive"))
      (node (ref "U4") (pin "8") (pinfunction "OUT_C_8") (pintype "output"))
    )
    (net (code "47") (name "Net-(U4-OUT_D)") (class "Default")
      (node (ref "R1F3") (pin "2") (pinfunction "2_2") (pintype "passive"))
      (node (ref "RV4") (pin "2") (pinfunction "2_2") (pintype "passive"))
      (node (ref "U4") (pin "14") (pinfunction "OUT_D_14") (pintype "output"))
    )
    (net (code "48") (name "unconnected-(U1-INH-Pad6)") (class "Default")
      (node (ref "U1") (pin "6") (pinfunction "INH_6") (pintype "input"))
    )
    (net (code "49") (name "unconnected-(U1-NC-Pad7)") (class "Default")
      (node (ref "U1") (pin "7") (pinfunction "NC_7") (pintype "passive"))
    )
    (net (code "50") (name "unconnected-(U1-Y0-Pad13)") (class "Default")
      (node (ref "U1") (pin "13") (pinfunction "Y0_13") (pintype "output"))
    )
    (net (code "51") (name "unconnected-(U1-Y6-Pad2)") (class "Default")
      (node (ref "U1") (pin "2") (pinfunction "Y6_2") (pintype "output"))
    )
    (net (code "52") (name "unconnected-(U1-Y7-Pad4)") (class "Default")
      (node (ref "U1") (pin "4") (pinfunction "Y7_4") (pintype "output"))
    )
    (net (code "53") (name "unconnected-(U2-NC-Pad3)") (class "Default")
      (node (ref "U2") (pin "3") (pinfunction "NC_3") (pintype "bidirectional"))
    )
  )
)
